# DAC_I2C.net
KiCad netlist of a schematic drawn in EAGLE
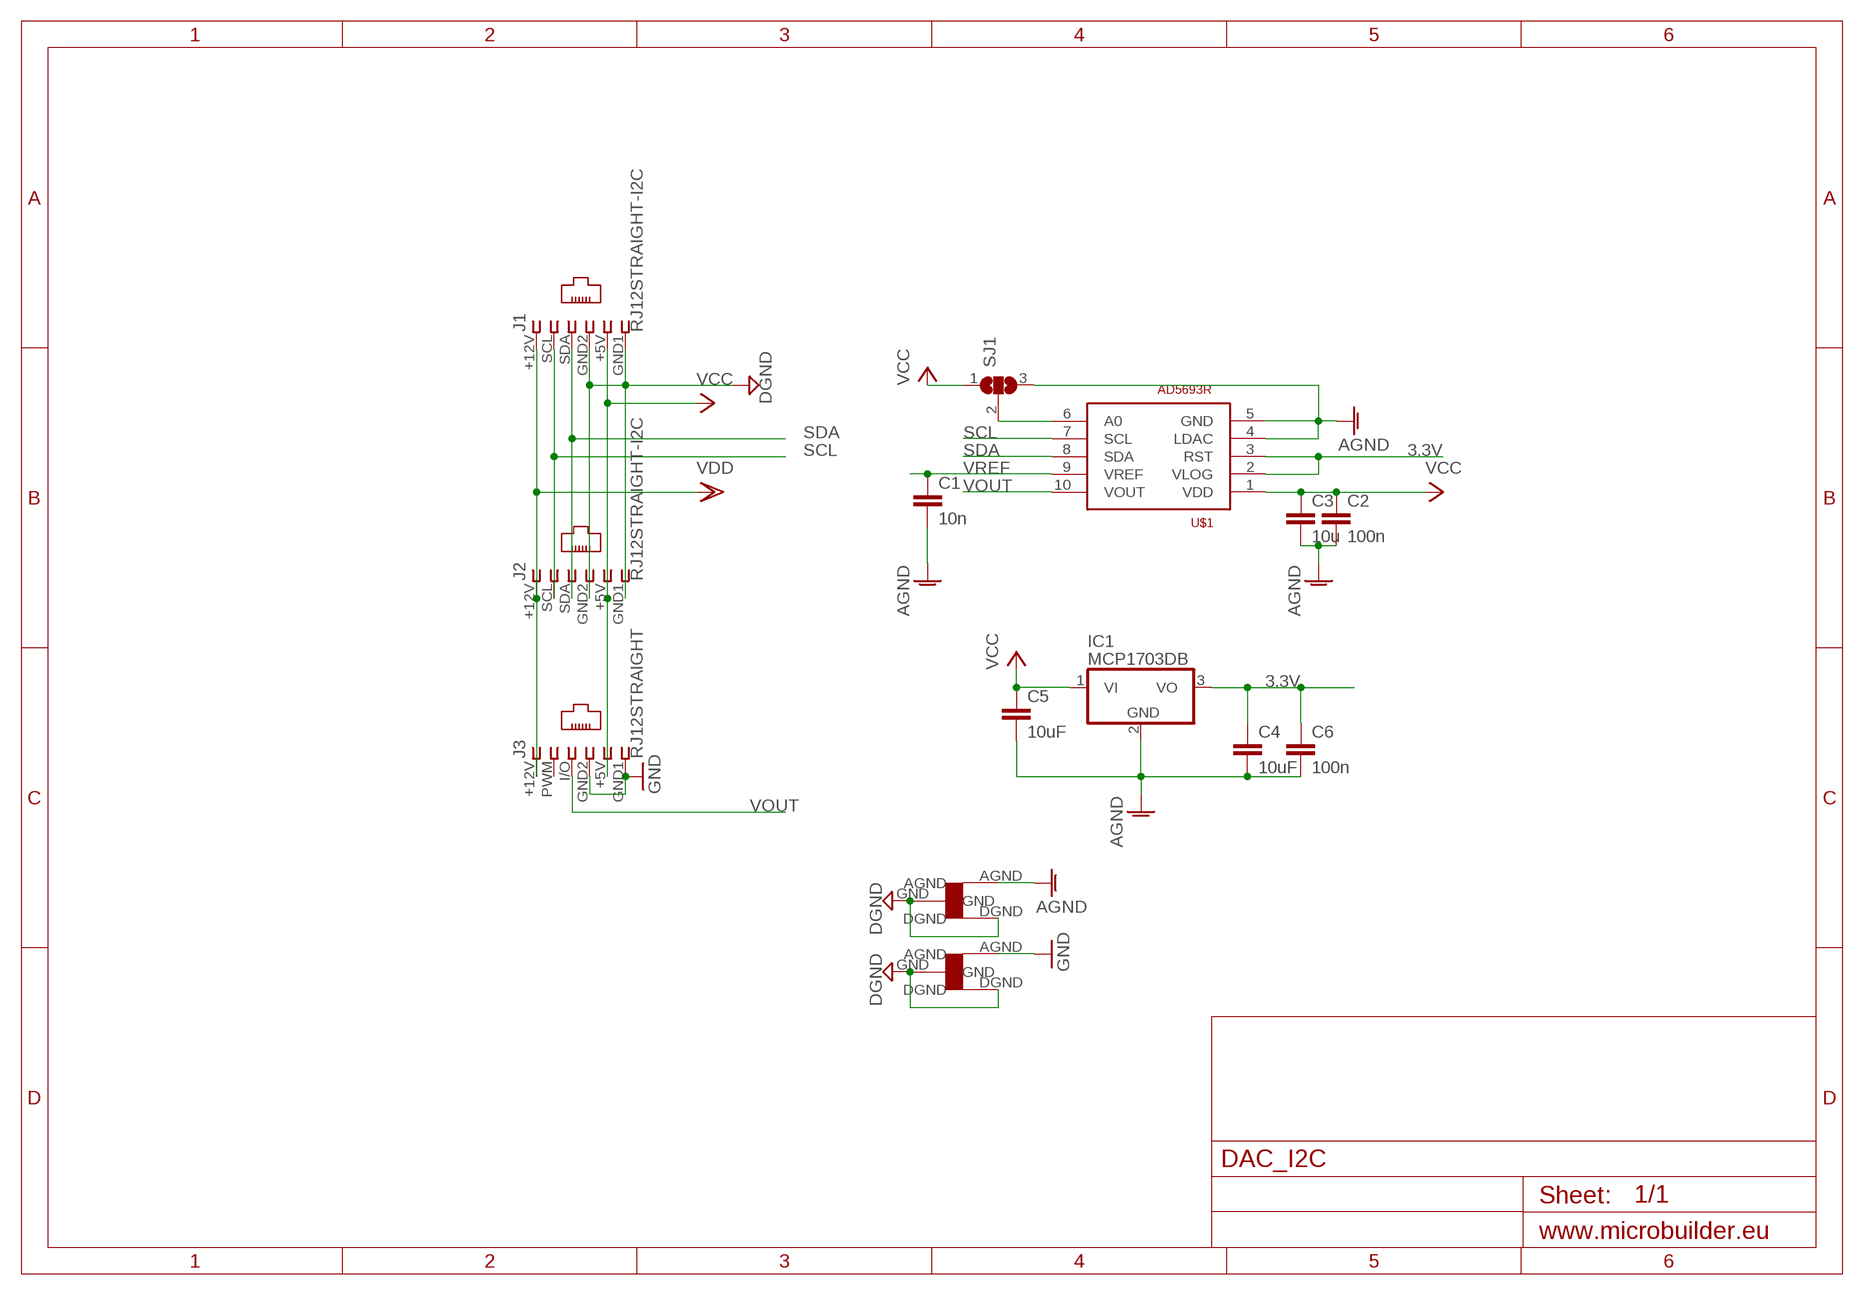
[diagram p0: schematic, sheet 1]

(export (version "E")
  (design (tool "Eeschema 10.0.6"))
  (components
    (comp (ref "C1")
      (value "10n")
      (footprint "eagle-import:C1206")
      (libsource (lib "eagle-import") (part "C-EUC1206"))
    )
    (comp (ref "C2")
      (value "100n")
      (footprint "eagle-import:C1206")
      (libsource (lib "eagle-import") (part "C-EUC1206"))
    )
    (comp (ref "C3")
      (value "10u")
      (footprint "eagle-import:C1206")
      (libsource (lib "eagle-import") (part "C-EUC1206"))
    )
    (comp (ref "C4")
      (value "10uF")
      (footprint "eagle-import:C1206")
      (libsource (lib "eagle-import") (part "C-EUC1206"))
    )
    (comp (ref "C5")
      (value "10uF")
      (footprint "eagle-import:C1206")
      (libsource (lib "eagle-import") (part "C-EUC1206"))
    )
    (comp (ref "C6")
      (value "100n")
      (footprint "eagle-import:C1206")
      (libsource (lib "eagle-import") (part "C-EUC1206"))
    )
    (comp (ref "IC1")
      (value "MCP1703DB")
      (footprint "eagle-import:SOT223")
      (libsource (lib "eagle-import") (part "MCP1703DB"))
    )
    (comp (ref "J1")
      (value "RJ12STRAIGHT-I2C")
      (footprint "eagle-import:RJ12-STRAIGHT-I2C")
      (libsource (lib "eagle-import") (part "RJ12STRAIGHT-I2C"))
    )
    (comp (ref "J2")
      (value "RJ12STRAIGHT-I2C")
      (footprint "eagle-import:RJ12-STRAIGHT-I2C")
      (libsource (lib "eagle-import") (part "RJ12STRAIGHT-I2C"))
    )
    (comp (ref "J3")
      (value "RJ12STRAIGHT")
      (footprint "eagle-import:RJ12-STRAIGHT")
      (libsource (lib "eagle-import") (part "RJ12STRAIGHT"))
    )
    (comp (ref "SJ1")
      (value "SJ2W")
      (footprint "eagle-import:SJ_2")
      (libsource (lib "eagle-import") (part "SJ2W"))
    )
    (comp (ref "U$1")
      (value "AD5693R")
      (footprint "eagle-import:MSOP10")
      (libsource (lib "eagle-import") (part "AD5693R"))
    )
    (comp (ref "U$2")
      (value "STARGND")
      (footprint "eagle-import:STAR")
      (libsource (lib "eagle-import") (part "STARGND"))
    )
    (comp (ref "U$5")
      (value "STARGND")
      (footprint "eagle-import:STAR")
      (libsource (lib "eagle-import") (part "STARGND"))
    )
  )
  (nets
    (net (code "1") (name "/3.3V") (class "Default")
      (node (ref "C4") (pin "1") (pinfunction "1_1") (pintype "passive"))
      (node (ref "C6") (pin "1") (pinfunction "1_1") (pintype "passive"))
      (node (ref "IC1") (pin "3") (pinfunction "VO_3") (pintype "passive"))
      (node (ref "U$1") (pin "2") (pinfunction "VLOG_2") (pintype "bidirectional"))
      (node (ref "U$1") (pin "3") (pinfunction "RST_3") (pintype "bidirectional"))
    )
    (net (code "2") (name "/SCL") (class "Default")
      (node (ref "J1") (pin "SCL") (pinfunction "2_SCL") (pintype "bidirectional"))
      (node (ref "J2") (pin "SCL") (pinfunction "2_SCL") (pintype "bidirectional"))
      (node (ref "U$1") (pin "7") (pinfunction "SCL_7") (pintype "bidirectional"))
    )
    (net (code "3") (name "/SDA") (class "Default")
      (node (ref "J1") (pin "SDA") (pinfunction "3_SDA") (pintype "bidirectional"))
      (node (ref "J2") (pin "SDA") (pinfunction "3_SDA") (pintype "bidirectional"))
      (node (ref "U$1") (pin "8") (pinfunction "SDA_8") (pintype "bidirectional"))
    )
    (net (code "4") (name "/VOUT") (class "Default")
      (node (ref "J3") (pin "I/O") (pinfunction "3_I/O") (pintype "bidirectional"))
      (node (ref "U$1") (pin "10") (pinfunction "VOUT_10") (pintype "bidirectional"))
    )
    (net (code "5") (name "/VREF") (class "Default")
      (node (ref "C1") (pin "1") (pinfunction "1_1") (pintype "passive"))
      (node (ref "U$1") (pin "9") (pinfunction "VREF_9") (pintype "bidirectional"))
    )
    (net (code "6") (name "AGND") (class "Default")
      (node (ref "C1") (pin "2") (pinfunction "2_2") (pintype "passive"))
      (node (ref "C2") (pin "2") (pinfunction "2_2") (pintype "passive"))
      (node (ref "C3") (pin "2") (pinfunction "2_2") (pintype "passive"))
      (node (ref "C4") (pin "2") (pinfunction "2_2") (pintype "passive"))
      (node (ref "C5") (pin "2") (pinfunction "2_2") (pintype "passive"))
      (node (ref "C6") (pin "2") (pinfunction "2_2") (pintype "passive"))
      (node (ref "IC1") (pin "2") (pinfunction "GND_2") (pintype "passive"))
      (node (ref "SJ1") (pin "3") (pinfunction "3_3") (pintype "passive"))
      (node (ref "U$1") (pin "4") (pinfunction "LDAC_4") (pintype "bidirectional"))
      (node (ref "U$1") (pin "5") (pinfunction "GND_5") (pintype "bidirectional"))
      (node (ref "U$5") (pin "AGND") (pinfunction "AGND_AGND") (pintype "output"))
    )
    (net (code "7") (name "DGND") (class "Default")
      (node (ref "J1") (pin "GND1") (pinfunction "6_GND1") (pintype "bidirectional"))
      (node (ref "J1") (pin "GND2") (pinfunction "4_GND2") (pintype "bidirectional"))
      (node (ref "J2") (pin "GND1") (pinfunction "6_GND1") (pintype "bidirectional"))
      (node (ref "J2") (pin "GND2") (pinfunction "4_GND2") (pintype "bidirectional"))
      (node (ref "U$2") (pin "DGND") (pinfunction "DGND_DGND") (pintype "output"))
      (node (ref "U$2") (pin "GND") (pinfunction "GND_GND") (pintype "power_in"))
      (node (ref "U$5") (pin "DGND") (pinfunction "DGND_DGND") (pintype "output"))
      (node (ref "U$5") (pin "GND") (pinfunction "GND_GND") (pintype "power_in"))
    )
    (net (code "8") (name "GND") (class "Default")
      (node (ref "J3") (pin "GND1") (pinfunction "6_GND1") (pintype "bidirectional"))
      (node (ref "J3") (pin "GND2") (pinfunction "4_GND2") (pintype "bidirectional"))
      (node (ref "U$2") (pin "AGND") (pinfunction "AGND_AGND") (pintype "output"))
    )
    (net (code "9") (name "Net-(U$1-A0)") (class "Default")
      (node (ref "SJ1") (pin "2") (pinfunction "2_2") (pintype "passive"))
      (node (ref "U$1") (pin "6") (pinfunction "A0_6") (pintype "bidirectional"))
    )
    (net (code "10") (name "VCC") (class "Default")
      (node (ref "C2") (pin "1") (pinfunction "1_1") (pintype "passive"))
      (node (ref "C3") (pin "1") (pinfunction "1_1") (pintype "passive"))
      (node (ref "C5") (pin "1") (pinfunction "1_1") (pintype "passive"))
      (node (ref "IC1") (pin "1") (pinfunction "VI_1") (pintype "input"))
      (node (ref "J1") (pin "+5V") (pinfunction "5_+5V") (pintype "bidirectional"))
      (node (ref "J2") (pin "+5V") (pinfunction "5_+5V") (pintype "bidirectional"))
      (node (ref "J3") (pin "+5V") (pinfunction "5_+5V") (pintype "bidirectional"))
      (node (ref "SJ1") (pin "1") (pinfunction "1_1") (pintype "passive"))
      (node (ref "U$1") (pin "1") (pinfunction "VDD_1") (pintype "bidirectional"))
    )
    (net (code "11") (name "VDD") (class "Default")
      (node (ref "J1") (pin "+12V") (pinfunction "1_+12V") (pintype "bidirectional"))
      (node (ref "J2") (pin "+12V") (pinfunction "1_+12V") (pintype "bidirectional"))
      (node (ref "J3") (pin "+12V") (pinfunction "1_+12V") (pintype "bidirectional"))
    )
    (net (code "12") (name "unconnected-(J3-2-PadPWM)") (class "Default")
      (node (ref "J3") (pin "PWM") (pinfunction "2_PWM") (pintype "bidirectional"))
    )
  )
)
